# door_v3.net
KiCad netlist of a schematic drawn in Altium Designer
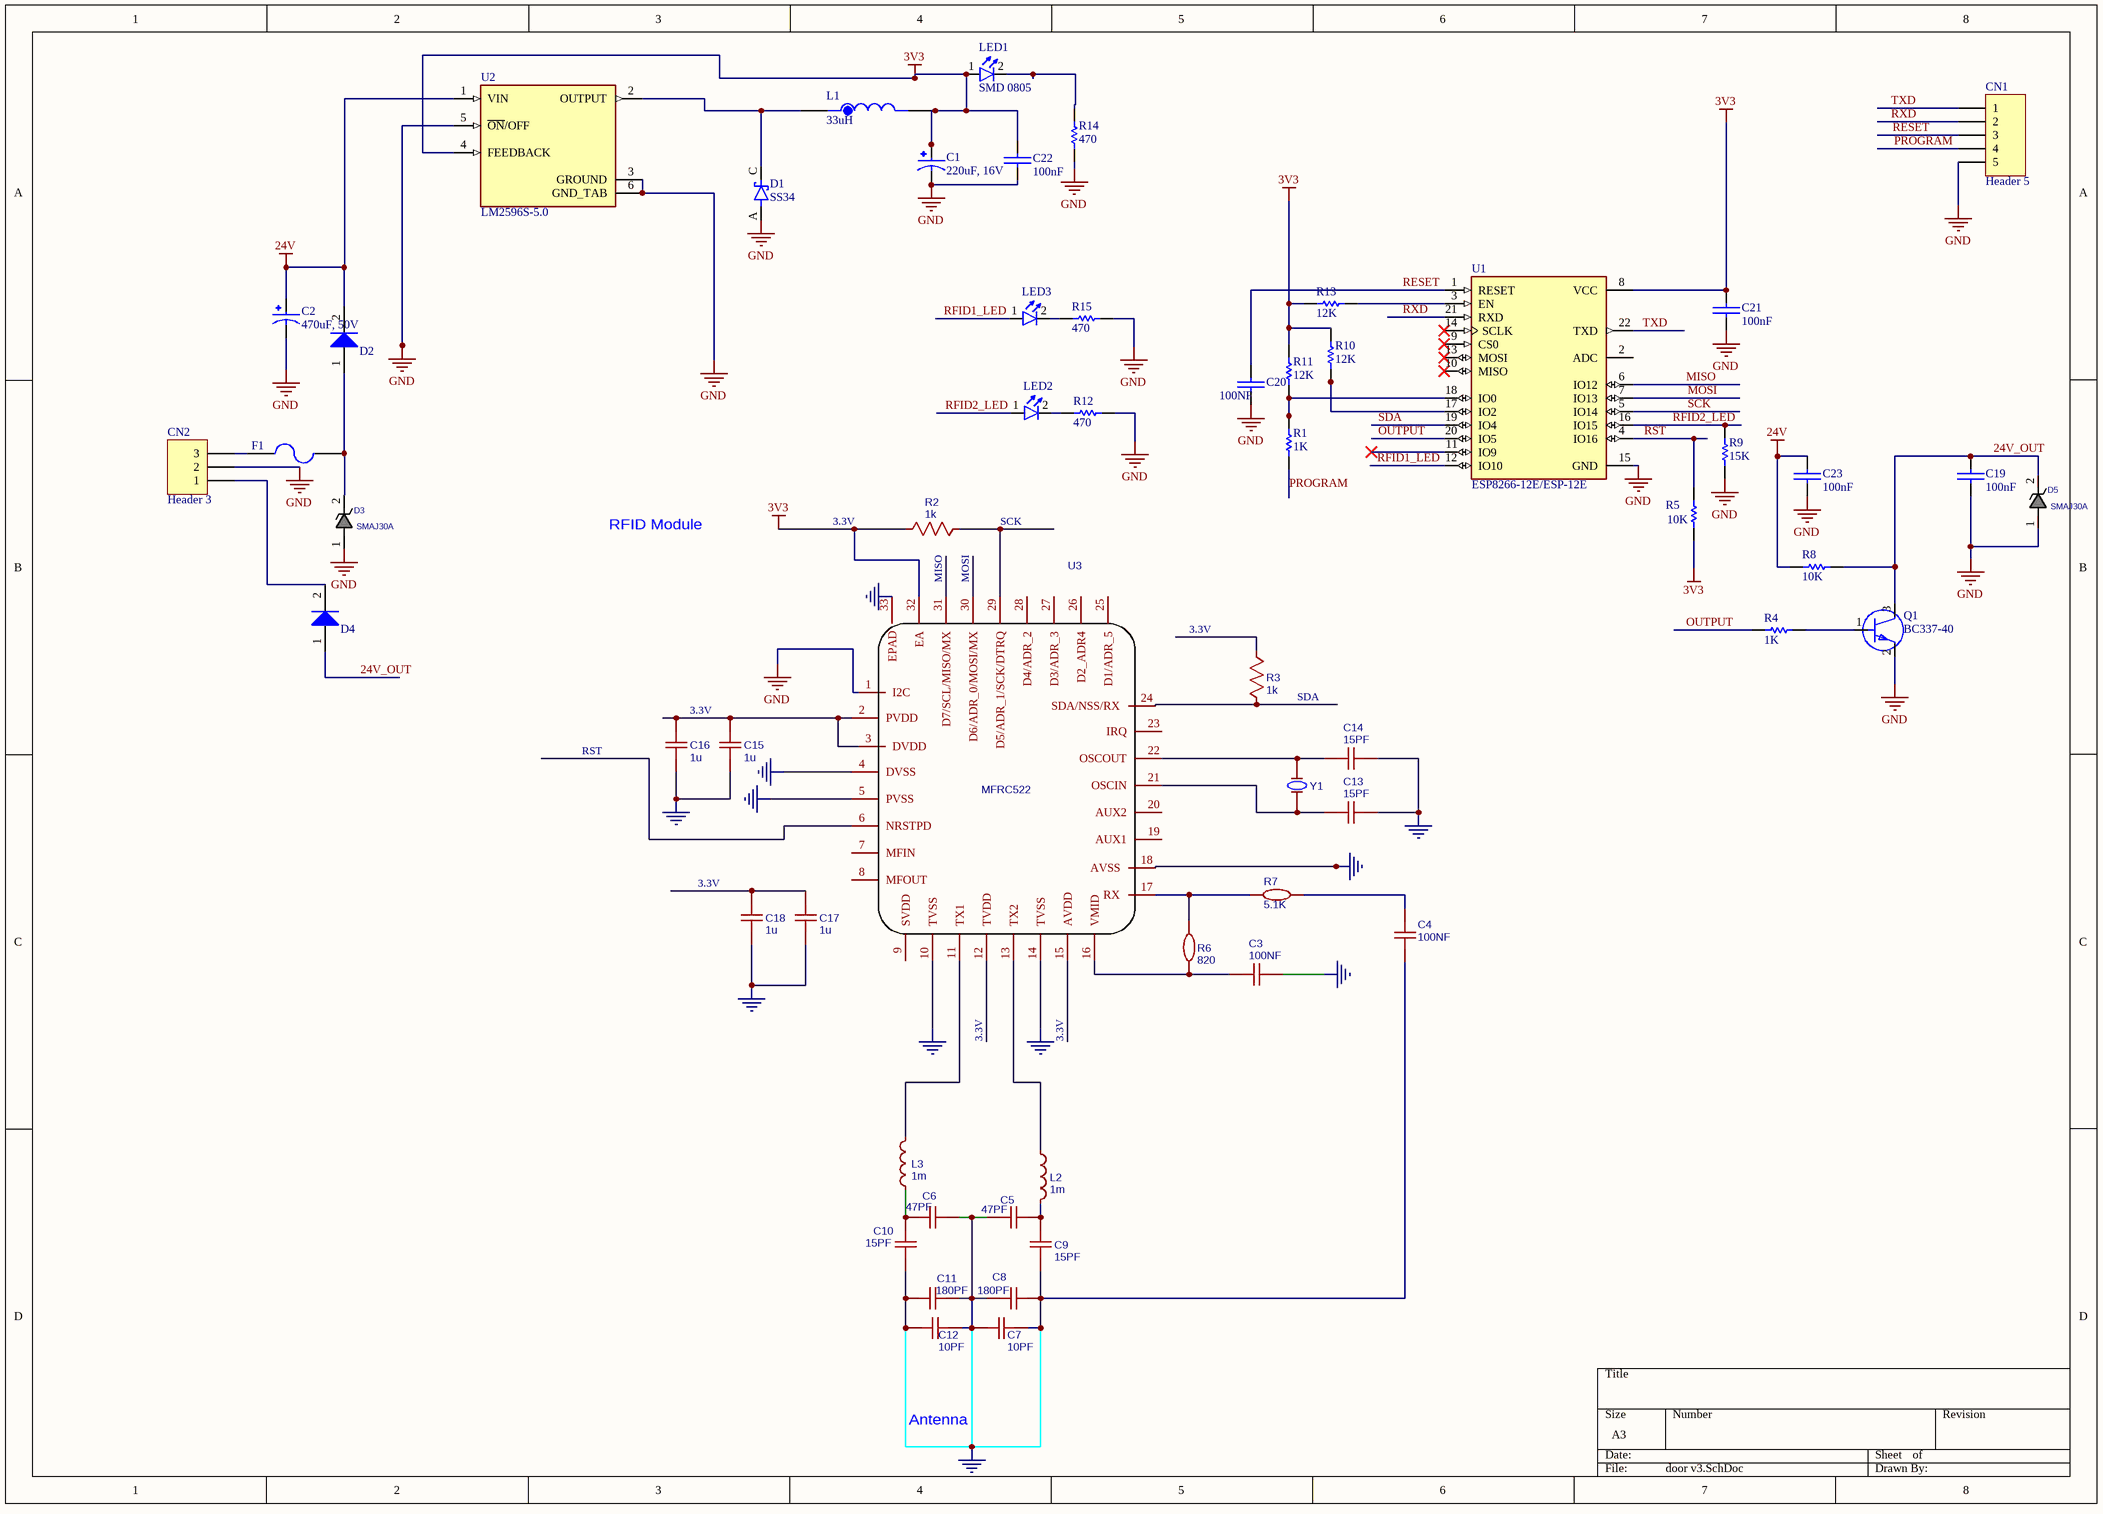
[diagram p0: door v3.SchDoc]

(export (version "E")
  (design (tool "Eeschema 10.0.6"))
  (components
    (comp (ref "C1")
      (value "220uF, 16V")
      (footprint "CAP_EEEFN0J681L")
      (description "CAP ALUM 680UF 20% 6.3V SMD")
      (fields (field (name "MF") "Panasonic") (field (name "MP") "EEEFN0J681L"))
      (libsource (lib "EEEFN0J681L") (part "EEEFN0J681L"))
    )
    (comp (ref "C2")
      (value "470uF, 50V")
      (footprint "CAP_EEEFN1V471UV")
      (description "CAP ALUM 680UF 20% 6.3V SMD")
      (fields (field (name "MF") "Panasonic") (field (name "MP") "EEEFN0J681L"))
      (libsource (lib "EEEFN0J681L") (part "EEEFN0J681L"))
    )
    (comp (ref "C3")
      (value "100NF")
      (footprint "0805C")
      (fields (field (name "BOM_MANUFACTURER PART") "?"))
      (libsource (lib "altium-import") (part "root_0_1u_"))
    )
    (comp (ref "C4")
      (value "100NF")
      (footprint "0805C")
      (fields (field (name "BOM_MANUFACTURER PART") "?"))
      (libsource (lib "altium-import") (part "root_1_1u_"))
    )
    (comp (ref "C5")
      (value "47PF")
      (footprint "0805C")
      (fields (field (name "BOM_MANUFACTURER PART") "?"))
      (libsource (lib "altium-import") (part "root_2_1u_"))
    )
    (comp (ref "C6")
      (value "47PF")
      (footprint "0805C")
      (fields (field (name "BOM_MANUFACTURER PART") "?"))
      (libsource (lib "altium-import") (part "root_2_1u_"))
    )
    (comp (ref "C7")
      (value "10PF")
      (footprint "0805C")
      (fields (field (name "BOM_MANUFACTURER PART") "?"))
      (libsource (lib "altium-import") (part "root_0_1u_"))
    )
    (comp (ref "C8")
      (value "180PF")
      (footprint "0805C")
      (fields (field (name "BOM_MANUFACTURER PART") "?"))
      (libsource (lib "altium-import") (part "root_2_1u_"))
    )
    (comp (ref "C9")
      (value "15PF")
      (footprint "0805C")
      (fields (field (name "BOM_MANUFACTURER PART") "?"))
      (libsource (lib "altium-import") (part "root_1_1u_"))
    )
    (comp (ref "C10")
      (value "15PF")
      (footprint "0805C")
      (fields (field (name "BOM_MANUFACTURER PART") "?"))
      (libsource (lib "altium-import") (part "root_1_1u_"))
    )
    (comp (ref "C11")
      (value "180PF")
      (footprint "0805C")
      (fields (field (name "BOM_MANUFACTURER PART") "?"))
      (libsource (lib "altium-import") (part "root_0_1u_"))
    )
    (comp (ref "C12")
      (value "10PF")
      (footprint "0805C")
      (fields (field (name "BOM_MANUFACTURER PART") "?"))
      (libsource (lib "altium-import") (part "root_0_1u_"))
    )
    (comp (ref "C13")
      (value "15PF")
      (footprint "0805C")
      (fields (field (name "BOM_MANUFACTURER PART") "?"))
      (libsource (lib "altium-import") (part "root_0_1u_"))
    )
    (comp (ref "C14")
      (value "15PF")
      (footprint "0805C")
      (fields (field (name "BOM_MANUFACTURER PART") "?"))
      (libsource (lib "altium-import") (part "root_0_1u_"))
    )
    (comp (ref "C15")
      (value "1u")
      (footprint "0805C")
      (fields (field (name "BOM_MANUFACTURER PART") "?"))
      (libsource (lib "altium-import") (part "root_1_1u_"))
    )
    (comp (ref "C16")
      (value "1u")
      (footprint "0805C")
      (fields (field (name "BOM_MANUFACTURER PART") "?"))
      (libsource (lib "altium-import") (part "root_1_1u_"))
    )
    (comp (ref "C17")
      (value "1u")
      (footprint "0805C")
      (fields (field (name "BOM_MANUFACTURER PART") "?"))
      (libsource (lib "altium-import") (part "root_1_1u_"))
    )
    (comp (ref "C18")
      (value "1u")
      (footprint "0805C")
      (fields (field (name "BOM_MANUFACTURER PART") "?"))
      (libsource (lib "altium-import") (part "root_1_1u_"))
    )
    (comp (ref "C19")
      (value "100nF")
      (footprint "0805C")
      (description "Bipolar Capacitor")
      (fields (field (name "VOLTAGE") "100V") (field (name "DESIGNER") "Saeid Jorablo"))
      (libsource (lib "General 2") (part "Cap-Bipolar"))
    )
    (comp (ref "C20")
      (value "100NF")
      (footprint "0805C")
      (description "Bipolar Capacitor")
      (fields (field (name "VOLTAGE") "100V") (field (name "DESIGNER") "Saeid Jorablo"))
      (libsource (lib "General 2") (part "Cap-Bipolar"))
    )
    (comp (ref "C21")
      (value "100nF")
      (footprint "0805C")
      (description "Bipolar Capacitor")
      (fields (field (name "VOLTAGE") "100V") (field (name "DESIGNER") "Saeid Jorablo"))
      (libsource (lib "General 2") (part "Cap-Bipolar"))
    )
    (comp (ref "C22")
      (value "100nF")
      (footprint "0805C")
      (description "Bipolar Capacitor")
      (fields (field (name "VOLTAGE") "100V") (field (name "DESIGNER") "Saeid Jorablo"))
      (libsource (lib "General 2") (part "Cap-Bipolar"))
    )
    (comp (ref "C23")
      (value "100nF")
      (footprint "0805C")
      (description "Bipolar Capacitor")
      (fields (field (name "VOLTAGE") "100V") (field (name "DESIGNER") "Saeid Jorablo"))
      (libsource (lib "General 2") (part "Cap-Bipolar"))
    )
    (comp (ref "CN1")
      (value "Header 5")
      (footprint "HDR1X5")
      (description "Header, 5-Pin")
      (fields (field (name "PUBLISHER") "Altium Limited"))
      (libsource (lib "Miscellaneous Connectors") (part "Header 5"))
    )
    (comp (ref "CN2")
      (value "Header 3")
      (footprint "MSTB 2,5/3-G-5,08")
      (description "Header, 3-Pin")
      (fields (field (name "PUBLISHER") "Altium Limited"))
      (libsource (lib "Miscellaneous Connectors") (part "Header 3"))
    )
    (comp (ref "D1")
      (value "SS34")
      (footprint "DIOM7959X265N")
      (description "Diode Schottky 40V 3A 2-Pin SMC T/R")
      (libsource (lib "SS34") (part "SS34"))
    )
    (comp (ref "D2")
      (value "1n4007")
      (footprint "DIOM4629X24N")
      (description "Standard Rectifiers")
      (fields (field (name "MANUFACTURER") "DC COMPONENTS") (field (name "DESIGNER") "Abbas Basereh"))
      (libsource (lib "General 1") (part "1n4007 SMD M7"))
    )
    (comp (ref "D3")
      (value "SMAJ30A")
      (footprint "SMA DIODE")
      (description "TVS, ESD PROTECT, 12VRWM, 30KV")
      (fields (field (name "MANF_P#") "SD12-01FTG, SD12C-01FTG") (field (name "MANF") "Littelfuse"))
      (libsource (lib "protect_tvs_esd_fuse") (part "TVS_SD12"))
    )
    (comp (ref "D4")
      (value "1n4007")
      (footprint "DIOM4629X24N")
      (description "Standard Rectifiers")
      (fields (field (name "MANUFACTURER") "DC COMPONENTS") (field (name "DESIGNER") "Abbas Basereh"))
      (libsource (lib "General 1") (part "1n4007 SMD M7"))
    )
    (comp (ref "D5")
      (value "SMAJ30A")
      (footprint "SMA DIODE")
      (description "TVS, ESD PROTECT, 12VRWM, 30KV")
      (fields (field (name "MANF_P#") "SD12-01FTG, SD12C-01FTG") (field (name "MANF") "Littelfuse"))
      (libsource (lib "protect_tvs_esd_fuse") (part "TVS_SD12"))
    )
    (comp (ref "F1")
      (value "F=1.0 A")
      (footprint "1206 FUSE")
      (description "SMD Fuses 1206")
      (fields (field (name "DESIGNER") "Abbas Basereh"))
      (libsource (lib "General 1") (part "Fuse SMD1206"))
    )
    (comp (ref "L1")
      (value "33uH")
      (footprint "IND_DRC-V-822K")
      (description "Radial Inductor with Leads,8200ÂµH, 0.13A,Q>20")
      (fields (field (name "MP") "DRC-V-822K") (field (name "MF") "Bel Fuse"))
      (libsource (lib "DRC-V-822K") (part "DRC-V-822K"))
    )
    (comp (ref "L2")
      (value "1m")
      (footprint "IND1206")
      (fields (field (name "BOM_MANUFACTURER PART") "?"))
      (libsource (lib "altium-import") (part "root_3_1m_"))
    )
    (comp (ref "L3")
      (value "1m")
      (footprint "IND1206")
      (fields (field (name "BOM_MANUFACTURER PART") "?"))
      (libsource (lib "altium-import") (part "root_1_1m_"))
    )
    (comp (ref "LED1")
      (value "Red")
      (footprint "LED_0805")
      (description "LED")
      (fields
        (field (name "SIZE") "SMD 0805")
        (field (name "DESIGNER") "Eng. Saeid Jorablo")
        (field (name "PUBLISHER") "SJ Unlimited")
      )
      (libsource (lib "Passive Components") (part "LED"))
    )
    (comp (ref "LED2")
      (value "Red")
      (footprint "LED_0805")
      (description "LED")
      (fields (field (name "DESIGNER") "Eng. Saeid Jorablo") (field (name "PUBLISHER") "SJ Unlimited"))
      (libsource (lib "Passive Components") (part "LED"))
    )
    (comp (ref "LED3")
      (value "Red")
      (footprint "LED_0805")
      (description "LED")
      (fields (field (name "DESIGNER") "Eng. Saeid Jorablo") (field (name "PUBLISHER") "SJ Unlimited"))
      (libsource (lib "Passive Components") (part "LED"))
    )
    (comp (ref "Q1")
      (value "BC337-40")
      (footprint "SOT23")
      (description "SMALL SIGNAL BIPOLAR TRANSISTOR")
      (fields (field (name "MP") "BC337") (field (name "MF") "NXP Semiconductors"))
      (libsource (lib "BC337") (part "BC337"))
    )
    (comp (ref "R1")
      (value "1K")
      (footprint "0805")
      (description "RES 1206")
      (fields (field (name "DESIGNER") "Abbas Basereh"))
      (libsource (lib "General 1") (part "RES 1206 0.25W"))
    )
    (comp (ref "R2")
      (value "1k")
      (footprint "0805")
      (fields (field (name "BOM_MANUFACTURER PART") "?"))
      (libsource (lib "altium-import") (part "root_2_1k_"))
    )
    (comp (ref "R3")
      (value "1k")
      (footprint "0805")
      (fields (field (name "BOM_MANUFACTURER PART") "?"))
      (libsource (lib "altium-import") (part "root_3_1k_"))
    )
    (comp (ref "R4")
      (value "1K")
      (footprint "0805")
      (description "RES 1206")
      (fields (field (name "DESIGNER") "Abbas Basereh"))
      (libsource (lib "General 1") (part "RES 1206 0.25W"))
    )
    (comp (ref "R5")
      (value "10K")
      (footprint "0805")
      (description "RES 1206")
      (fields (field (name "DESIGNER") "Abbas Basereh"))
      (libsource (lib "General 1") (part "RES 1206 0.25W"))
    )
    (comp (ref "R6")
      (value "820")
      (footprint "0805")
      (fields (field (name "BOM_MANUFACTURER PART") "?"))
      (libsource (lib "altium-import") (part "root_1_1k_"))
    )
    (comp (ref "R7")
      (value "5.1K")
      (footprint "0805")
      (fields (field (name "BOM_MANUFACTURER PART") "?"))
      (libsource (lib "") (part "root_2_1k__1"))
    )
    (comp (ref "R8")
      (value "10K")
      (footprint "0805")
      (description "RES 1206")
      (fields (field (name "DESIGNER") "Abbas Basereh"))
      (libsource (lib "General 1") (part "RES 1206 0.25W"))
    )
    (comp (ref "R9")
      (value "15K")
      (footprint "0805")
      (description "RES 1206")
      (fields (field (name "DESIGNER") "Abbas Basereh"))
      (libsource (lib "General 1") (part "RES 1206 0.25W"))
    )
    (comp (ref "R10")
      (value "12K")
      (footprint "0805")
      (description "RES 1206")
      (fields (field (name "DESIGNER") "Abbas Basereh"))
      (libsource (lib "General 1") (part "RES 1206 0.25W"))
    )
    (comp (ref "R11")
      (value "12K")
      (footprint "0805")
      (description "RES 1206")
      (fields (field (name "DESIGNER") "Abbas Basereh"))
      (libsource (lib "General 1") (part "RES 1206 0.25W"))
    )
    (comp (ref "R12")
      (value "470")
      (footprint "0805")
      (description "RES 1206")
      (fields (field (name "DESIGNER") "Abbas Basereh"))
      (libsource (lib "General 1") (part "RES 1206 0.25W"))
    )
    (comp (ref "R13")
      (value "12K")
      (footprint "0805")
      (description "RES 1206")
      (fields (field (name "DESIGNER") "Abbas Basereh"))
      (libsource (lib "General 1") (part "RES 1206 0.25W"))
    )
    (comp (ref "R14")
      (value "470")
      (footprint "0805")
      (description "RES 1206")
      (fields (field (name "DESIGNER") "Abbas Basereh"))
      (libsource (lib "General 1") (part "RES 1206 0.25W"))
    )
    (comp (ref "R15")
      (value "470")
      (footprint "0805")
      (description "RES 1206")
      (fields (field (name "DESIGNER") "Abbas Basereh"))
      (libsource (lib "General 1") (part "RES 1206 0.25W"))
    )
    (comp (ref "U1")
      (value "ESP8266-12E/ESP-12E")
      (footprint "XCVR_ESP8266-12E/ESP-12E")
      (description "ESP-12E WiFi Module")
      (libsource (lib "ESP8266-12E_ESP-12E") (part "ESP8266-12E/ESP-12E"))
    )
    (comp (ref "U2")
      (value "LM2596S-5.0")
      (footprint "TO170P1524X483-6N")
      (libsource (lib "LM2596S-5.0") (part "LM2596S-5.0"))
    )
    (comp (ref "U3")
      (value "MFRC522")
      (footprint "HVQFN32")
      (fields (field (name "BOM_MANUFACTURER PART") "?") (field (name "CONTRIBUTOR") "GerryChen"))
      (libsource (lib "altium-import") (part "root_0_MFRC522_"))
    )
    (comp (ref "Y1")
      (value "XTALfast")
      (footprint "XTAL")
      (fields (field (name "BOM_MANUFACTURER PART") "?"))
      (libsource (lib "altium-import") (part "root_1_XTALfast_"))
    )
  )
  (nets
    (net (code "1") (name "/24V_OUT") (class "Default")
      (node (ref "C19") (pin "1") (pinfunction "+_1") (pintype "passive"))
      (node (ref "D4") (pin "1") (pinfunction "A_1") (pintype "passive"))
      (node (ref "D5") (pin "2") (pinfunction "2_2") (pintype "passive"))
      (node (ref "Q1") (pin "3") (pinfunction "C_3") (pintype "passive"))
      (node (ref "R8") (pin "2") (pinfunction "2_2") (pintype "passive"))
    )
    (net (code "2") (name "/MISO") (class "Default")
      (node (ref "U1") (pin "6") (pinfunction "IO12_6") (pintype "bidirectional"))
      (node (ref "U3") (pin "31") (pinfunction "D7/SCL/MISO/MX_31") (pintype "passive"))
    )
    (net (code "3") (name "/MOSI") (class "Default")
      (node (ref "U1") (pin "7") (pinfunction "IO13_7") (pintype "bidirectional"))
      (node (ref "U3") (pin "30") (pinfunction "D6/ADR_0/MOSI/MX_30") (pintype "passive"))
    )
    (net (code "4") (name "/OUTPUT") (class "Default")
      (node (ref "R4") (pin "2") (pinfunction "2_2") (pintype "passive"))
      (node (ref "U1") (pin "20") (pinfunction "IO5_20") (pintype "bidirectional"))
    )
    (net (code "5") (name "/PROGRAM") (class "Default")
      (node (ref "CN1") (pin "4") (pinfunction "4_4") (pintype "passive"))
      (node (ref "R1") (pin "1") (pinfunction "1_1") (pintype "passive"))
    )
    (net (code "6") (name "/RESET") (class "Default")
      (node (ref "C20") (pin "1") (pinfunction "+_1") (pintype "passive"))
      (node (ref "CN1") (pin "3") (pinfunction "3_3") (pintype "passive"))
      (node (ref "U1") (pin "1") (pinfunction "RESET_1") (pintype "input"))
    )
    (net (code "7") (name "/RFID1_LED") (class "Default")
      (node (ref "LED3") (pin "1") (pinfunction "A_1") (pintype "passive"))
      (node (ref "U1") (pin "12") (pinfunction "IO10_12") (pintype "bidirectional"))
    )
    (net (code "8") (name "/RFID2_LED") (class "Default")
      (node (ref "LED2") (pin "1") (pinfunction "A_1") (pintype "passive"))
      (node (ref "R9") (pin "2") (pinfunction "2_2") (pintype "passive"))
      (node (ref "U1") (pin "16") (pinfunction "IO15_16") (pintype "bidirectional"))
    )
    (net (code "9") (name "/RST") (class "Default")
      (node (ref "R5") (pin "2") (pinfunction "2_2") (pintype "passive"))
      (node (ref "U1") (pin "4") (pinfunction "IO16_4") (pintype "bidirectional"))
      (node (ref "U3") (pin "6") (pinfunction "NRSTPD_6") (pintype "passive"))
    )
    (net (code "10") (name "/RXD") (class "Default")
      (node (ref "CN1") (pin "2") (pinfunction "2_2") (pintype "passive"))
      (node (ref "U1") (pin "21") (pinfunction "RXD_21") (pintype "input"))
    )
    (net (code "11") (name "/SCK") (class "Default")
      (node (ref "R2") (pin "1") (pinfunction "1_1") (pintype "passive"))
      (node (ref "U1") (pin "5") (pinfunction "IO14_5") (pintype "bidirectional"))
      (node (ref "U3") (pin "29") (pinfunction "D5/ADR_1/SCK/DTRQ_29") (pintype "passive"))
    )
    (net (code "12") (name "/SDA") (class "Default")
      (node (ref "R3") (pin "2") (pinfunction "2_2") (pintype "passive"))
      (node (ref "U1") (pin "19") (pinfunction "IO4_19") (pintype "bidirectional"))
      (node (ref "U3") (pin "24") (pinfunction "SDA/NSS/RX_24") (pintype "passive"))
    )
    (net (code "13") (name "/TXD") (class "Default")
      (node (ref "CN1") (pin "1") (pinfunction "1_1") (pintype "passive"))
      (node (ref "U1") (pin "22") (pinfunction "TXD_22") (pintype "output"))
    )
    (net (code "14") (name "3V3") (class "Default")
      (node (ref "C1") (pin "1") (pinfunction "1_1") (pintype "passive"))
      (node (ref "C15") (pin "2") (pinfunction "2_2") (pintype "passive"))
      (node (ref "C16") (pin "2") (pinfunction "2_2") (pintype "passive"))
      (node (ref "C17") (pin "2") (pinfunction "2_2") (pintype "passive"))
      (node (ref "C18") (pin "2") (pinfunction "2_2") (pintype "passive"))
      (node (ref "C21") (pin "1") (pinfunction "+_1") (pintype "passive"))
      (node (ref "C22") (pin "1") (pinfunction "+_1") (pintype "passive"))
      (node (ref "L1") (pin "2") (pinfunction "2_2") (pintype "passive"))
      (node (ref "LED1") (pin "1") (pinfunction "A_1") (pintype "passive"))
      (node (ref "R10") (pin "2") (pinfunction "2_2") (pintype "passive"))
      (node (ref "R11") (pin "2") (pinfunction "2_2") (pintype "passive"))
      (node (ref "R13") (pin "2") (pinfunction "2_2") (pintype "passive"))
      (node (ref "R2") (pin "2") (pinfunction "2_2") (pintype "passive"))
      (node (ref "R3") (pin "1") (pinfunction "1_1") (pintype "passive"))
      (node (ref "R5") (pin "1") (pinfunction "1_1") (pintype "passive"))
      (node (ref "U1") (pin "8") (pinfunction "VCC_8") (pintype "power_in"))
      (node (ref "U2") (pin "4") (pinfunction "FEEDBACK_4") (pintype "input"))
      (node (ref "U3") (pin "12") (pinfunction "TVDD_12") (pintype "passive"))
      (node (ref "U3") (pin "15") (pinfunction "AVDD_15") (pintype "passive"))
      (node (ref "U3") (pin "2") (pinfunction "PVDD_2") (pintype "passive"))
      (node (ref "U3") (pin "3") (pinfunction "DVDD_3") (pintype "passive"))
      (node (ref "U3") (pin "32") (pinfunction "EA_32") (pintype "passive"))
    )
    (net (code "15") (name "24V") (class "Default")
      (node (ref "C2") (pin "1") (pinfunction "1_1") (pintype "passive"))
      (node (ref "C23") (pin "1") (pinfunction "+_1") (pintype "passive"))
      (node (ref "D2") (pin "2") (pinfunction "K_2") (pintype "passive"))
      (node (ref "R8") (pin "1") (pinfunction "1_1") (pintype "passive"))
      (node (ref "U2") (pin "1") (pinfunction "VIN_1") (pintype "input"))
    )
    (net (code "16") (name "GND") (class "Default")
      (node (ref "C1") (pin "2") (pinfunction "2_2") (pintype "passive"))
      (node (ref "C10") (pin "1") (pinfunction "1_1") (pintype "passive"))
      (node (ref "C11") (pin "1") (pinfunction "1_1") (pintype "passive"))
      (node (ref "C11") (pin "2") (pinfunction "2_2") (pintype "passive"))
      (node (ref "C12") (pin "1") (pinfunction "1_1") (pintype "passive"))
      (node (ref "C12") (pin "2") (pinfunction "2_2") (pintype "passive"))
      (node (ref "C13") (pin "2") (pinfunction "2_2") (pintype "passive"))
      (node (ref "C14") (pin "2") (pinfunction "2_2") (pintype "passive"))
      (node (ref "C15") (pin "1") (pinfunction "1_1") (pintype "passive"))
      (node (ref "C16") (pin "1") (pinfunction "1_1") (pintype "passive"))
      (node (ref "C17") (pin "1") (pinfunction "1_1") (pintype "passive"))
      (node (ref "C18") (pin "1") (pinfunction "1_1") (pintype "passive"))
      (node (ref "C19") (pin "2") (pinfunction "-_2") (pintype "passive"))
      (node (ref "C2") (pin "2") (pinfunction "2_2") (pintype "passive"))
      (node (ref "C20") (pin "2") (pinfunction "-_2") (pintype "passive"))
      (node (ref "C21") (pin "2") (pinfunction "-_2") (pintype "passive"))
      (node (ref "C22") (pin "2") (pinfunction "-_2") (pintype "passive"))
      (node (ref "C23") (pin "2") (pinfunction "-_2") (pintype "passive"))
      (node (ref "C3") (pin "2") (pinfunction "2_2") (pintype "passive"))
      (node (ref "C4") (pin "1") (pinfunction "1_1") (pintype "passive"))
      (node (ref "C5") (pin "2") (pinfunction "2_2") (pintype "passive"))
      (node (ref "C6") (pin "1") (pinfunction "1_1") (pintype "passive"))
      (node (ref "C7") (pin "1") (pinfunction "1_1") (pintype "passive"))
      (node (ref "C7") (pin "2") (pinfunction "2_2") (pintype "passive"))
      (node (ref "C8") (pin "1") (pinfunction "1_1") (pintype "passive"))
      (node (ref "C8") (pin "2") (pinfunction "2_2") (pintype "passive"))
      (node (ref "C9") (pin "1") (pinfunction "1_1") (pintype "passive"))
      (node (ref "CN1") (pin "5") (pinfunction "5_5") (pintype "passive"))
      (node (ref "CN2") (pin "2") (pinfunction "2_2") (pintype "passive"))
      (node (ref "D1") (pin "A") (pinfunction "A_A") (pintype "passive"))
      (node (ref "D3") (pin "1") (pinfunction "1_1") (pintype "passive"))
      (node (ref "D5") (pin "1") (pinfunction "1_1") (pintype "passive"))
      (node (ref "Q1") (pin "2") (pinfunction "E_2") (pintype "passive"))
      (node (ref "R12") (pin "1") (pinfunction "1_1") (pintype "passive"))
      (node (ref "R14") (pin "1") (pinfunction "1_1") (pintype "passive"))
      (node (ref "R15") (pin "1") (pinfunction "1_1") (pintype "passive"))
      (node (ref "R9") (pin "1") (pinfunction "1_1") (pintype "passive"))
      (node (ref "U1") (pin "15") (pinfunction "GND_15") (pintype "power_in"))
      (node (ref "U2") (pin "3") (pinfunction "GROUND_3") (pintype "power_in"))
      (node (ref "U2") (pin "5") (pinfunction "~{ON}/OFF_5") (pintype "input"))
      (node (ref "U2") (pin "6") (pinfunction "GND_TAB_6") (pintype "power_in"))
      (node (ref "U3") (pin "1") (pinfunction "I2C_1") (pintype "passive"))
      (node (ref "U3") (pin "10") (pinfunction "TVSS_10") (pintype "passive"))
      (node (ref "U3") (pin "14") (pinfunction "TVSS_14") (pintype "passive"))
      (node (ref "U3") (pin "18") (pinfunction "AVSS_18") (pintype "passive"))
      (node (ref "U3") (pin "33") (pinfunction "EPAD_33") (pintype "passive"))
      (node (ref "U3") (pin "4") (pinfunction "DVSS_4") (pintype "passive"))
      (node (ref "U3") (pin "5") (pinfunction "PVSS_5") (pintype "passive"))
    )
    (net (code "17") (name "Net-(C4-Pad2)") (class "Default")
      (node (ref "C4") (pin "2") (pinfunction "2_2") (pintype "passive"))
      (node (ref "R7") (pin "1") (pinfunction "1_1") (pintype "passive"))
    )
    (net (code "18") (name "Net-(C5-Pad1)") (class "Default")
      (node (ref "C5") (pin "1") (pinfunction "1_1") (pintype "passive"))
      (node (ref "C9") (pin "2") (pinfunction "2_2") (pintype "passive"))
      (node (ref "L2") (pin "2") (pinfunction "2_2") (pintype "passive"))
    )
    (net (code "19") (name "Net-(C10-Pad2)") (class "Default")
      (node (ref "C10") (pin "2") (pinfunction "2_2") (pintype "passive"))
      (node (ref "C6") (pin "2") (pinfunction "2_2") (pintype "passive"))
      (node (ref "L3") (pin "1") (pinfunction "1_1") (pintype "passive"))
    )
    (net (code "20") (name "Net-(CN2-Pad3)") (class "Default")
      (node (ref "CN2") (pin "3") (pinfunction "3_3") (pintype "passive"))
      (node (ref "F1") (pin "1") (pinfunction "1_1") (pintype "passive"))
    )
    (net (code "21") (name "Net-(D1-K)") (class "Default")
      (node (ref "D1") (pin "C") (pinfunction "K_C") (pintype "passive"))
      (node (ref "L1") (pin "1") (pinfunction "1_1") (pintype "passive"))
      (node (ref "U2") (pin "2") (pinfunction "OUTPUT_2") (pintype "output"))
    )
    (net (code "22") (name "Net-(D2-A)") (class "Default")
      (node (ref "D2") (pin "1") (pinfunction "A_1") (pintype "passive"))
      (node (ref "D3") (pin "2") (pinfunction "2_2") (pintype "passive"))
      (node (ref "F1") (pin "2") (pinfunction "2_2") (pintype "passive"))
    )
    (net (code "23") (name "Net-(D4-K)") (class "Default")
      (node (ref "CN2") (pin "1") (pinfunction "1_1") (pintype "passive"))
      (node (ref "D4") (pin "2") (pinfunction "K_2") (pintype "passive"))
    )
    (net (code "24") (name "Net-(LED1-K)") (class "Default")
      (node (ref "LED1") (pin "2") (pinfunction "K_2") (pintype "passive"))
      (node (ref "R14") (pin "2") (pinfunction "2_2") (pintype "passive"))
    )
    (net (code "25") (name "Net-(LED2-K)") (class "Default")
      (node (ref "LED2") (pin "2") (pinfunction "K_2") (pintype "passive"))
      (node (ref "R12") (pin "2") (pinfunction "2_2") (pintype "passive"))
    )
    (net (code "26") (name "Net-(LED3-K)") (class "Default")
      (node (ref "LED3") (pin "2") (pinfunction "K_2") (pintype "passive"))
      (node (ref "R15") (pin "2") (pinfunction "2_2") (pintype "passive"))
    )
    (net (code "27") (name "Net-(Q1-B)") (class "Default")
      (node (ref "Q1") (pin "1") (pinfunction "B_1") (pintype "passive"))
      (node (ref "R4") (pin "1") (pinfunction "1_1") (pintype "passive"))
    )
    (net (code "28") (name "Net-(U1-EN)") (class "Default")
      (node (ref "R13") (pin "1") (pinfunction "1_1") (pintype "passive"))
      (node (ref "U1") (pin "3") (pinfunction "EN_3") (pintype "input"))
    )
    (net (code "29") (name "Net-(U1-IO0)") (class "Default")
      (node (ref "R1") (pin "2") (pinfunction "2_2") (pintype "passive"))
      (node (ref "R11") (pin "1") (pinfunction "1_1") (pintype "passive"))
      (node (ref "U1") (pin "18") (pinfunction "IO0_18") (pintype "bidirectional"))
    )
    (net (code "30") (name "Net-(U1-IO2)") (class "Default")
      (node (ref "R10") (pin "1") (pinfunction "1_1") (pintype "passive"))
      (node (ref "U1") (pin "17") (pinfunction "IO2_17") (pintype "bidirectional"))
    )
    (net (code "31") (name "Net-(U3-OSCIN)") (class "Default")
      (node (ref "C13") (pin "1") (pinfunction "1_1") (pintype "passive"))
      (node (ref "U3") (pin "21") (pinfunction "OSCIN_21") (pintype "passive"))
      (node (ref "Y1") (pin "1") (pinfunction "OSC1_1") (pintype "passive"))
    )
    (net (code "32") (name "Net-(U3-OSCOUT)") (class "Default")
      (node (ref "C14") (pin "1") (pinfunction "1_1") (pintype "passive"))
      (node (ref "U3") (pin "22") (pinfunction "OSCOUT_22") (pintype "passive"))
      (node (ref "Y1") (pin "2") (pinfunction "OSC2_2") (pintype "passive"))
    )
    (net (code "33") (name "Net-(U3-RX)") (class "Default")
      (node (ref "R6") (pin "2") (pinfunction "2_2") (pintype "passive"))
      (node (ref "R7") (pin "2") (pinfunction "2_2") (pintype "passive"))
      (node (ref "U3") (pin "17") (pinfunction "RX_17") (pintype "passive"))
    )
    (net (code "34") (name "Net-(U3-TX1)") (class "Default")
      (node (ref "L3") (pin "2") (pinfunction "2_2") (pintype "passive"))
      (node (ref "U3") (pin "11") (pinfunction "TX1_11") (pintype "passive"))
    )
    (net (code "35") (name "Net-(U3-TX2)") (class "Default")
      (node (ref "L2") (pin "1") (pinfunction "1_1") (pintype "passive"))
      (node (ref "U3") (pin "13") (pinfunction "TX2_13") (pintype "passive"))
    )
    (net (code "36") (name "Net-(U3-VMID)") (class "Default")
      (node (ref "C3") (pin "1") (pinfunction "1_1") (pintype "passive"))
      (node (ref "R6") (pin "1") (pinfunction "1_1") (pintype "passive"))
      (node (ref "U3") (pin "16") (pinfunction "VMID_16") (pintype "passive"))
    )
    (net (code "37") (name "unconnected-(U1-ADC-Pad2)") (class "Default")
      (node (ref "U1") (pin "2") (pinfunction "ADC_2") (pintype "passive"))
    )
    (net (code "38") (name "unconnected-(U1-CS0-Pad9)") (class "Default")
      (node (ref "U1") (pin "9") (pinfunction "CS0_9") (pintype "input+no_connect"))
    )
    (net (code "39") (name "unconnected-(U1-IO9-Pad11)") (class "Default")
      (node (ref "U1") (pin "11") (pinfunction "IO9_11") (pintype "bidirectional+no_connect"))
    )
    (net (code "40") (name "unconnected-(U1-MISO-Pad10)") (class "Default")
      (node (ref "U1") (pin "10") (pinfunction "MISO_10") (pintype "bidirectional+no_connect"))
    )
    (net (code "41") (name "unconnected-(U1-MOSI-Pad13)") (class "Default")
      (node (ref "U1") (pin "13") (pinfunction "MOSI_13") (pintype "bidirectional+no_connect"))
    )
    (net (code "42") (name "unconnected-(U1-SCLK-Pad14)") (class "Default")
      (node (ref "U1") (pin "14") (pinfunction "SCLK_14") (pintype "input+no_connect"))
    )
    (net (code "43") (name "unconnected-(U3-AUX1-Pad19)") (class "Default")
      (node (ref "U3") (pin "19") (pinfunction "AUX1_19") (pintype "passive"))
    )
    (net (code "44") (name "unconnected-(U3-AUX2-Pad20)") (class "Default")
      (node (ref "U3") (pin "20") (pinfunction "AUX2_20") (pintype "passive"))
    )
    (net (code "45") (name "unconnected-(U3-D1{slash}ADR_5-Pad25)") (class "Default")
      (node (ref "U3") (pin "25") (pinfunction "D1/ADR_5_25") (pintype "passive"))
    )
    (net (code "46") (name "unconnected-(U3-D2_ADR4-Pad26)") (class "Default")
      (node (ref "U3") (pin "26") (pinfunction "D2_ADR4_26") (pintype "passive"))
    )
    (net (code "47") (name "unconnected-(U3-D3{slash}ADR_3-Pad27)") (class "Default")
      (node (ref "U3") (pin "27") (pinfunction "D3/ADR_3_27") (pintype "passive"))
    )
    (net (code "48") (name "unconnected-(U3-D4{slash}ADR_2-Pad28)") (class "Default")
      (node (ref "U3") (pin "28") (pinfunction "D4/ADR_2_28") (pintype "passive"))
    )
    (net (code "49") (name "unconnected-(U3-IRQ-Pad23)") (class "Default")
      (node (ref "U3") (pin "23") (pinfunction "IRQ_23") (pintype "passive"))
    )
    (net (code "50") (name "unconnected-(U3-MFIN-Pad7)") (class "Default")
      (node (ref "U3") (pin "7") (pinfunction "MFIN_7") (pintype "passive"))
    )
    (net (code "51") (name "unconnected-(U3-MFOUT-Pad8)") (class "Default")
      (node (ref "U3") (pin "8") (pinfunction "MFOUT_8") (pintype "passive"))
    )
    (net (code "52") (name "unconnected-(U3-SVDD-Pad9)") (class "Default")
      (node (ref "U3") (pin "9") (pinfunction "SVDD_9") (pintype "passive"))
    )
  )
)
